# CHM_CPU_FPGA_CLAMP.net
KiCad netlist of a schematic drawn in Altium Designer
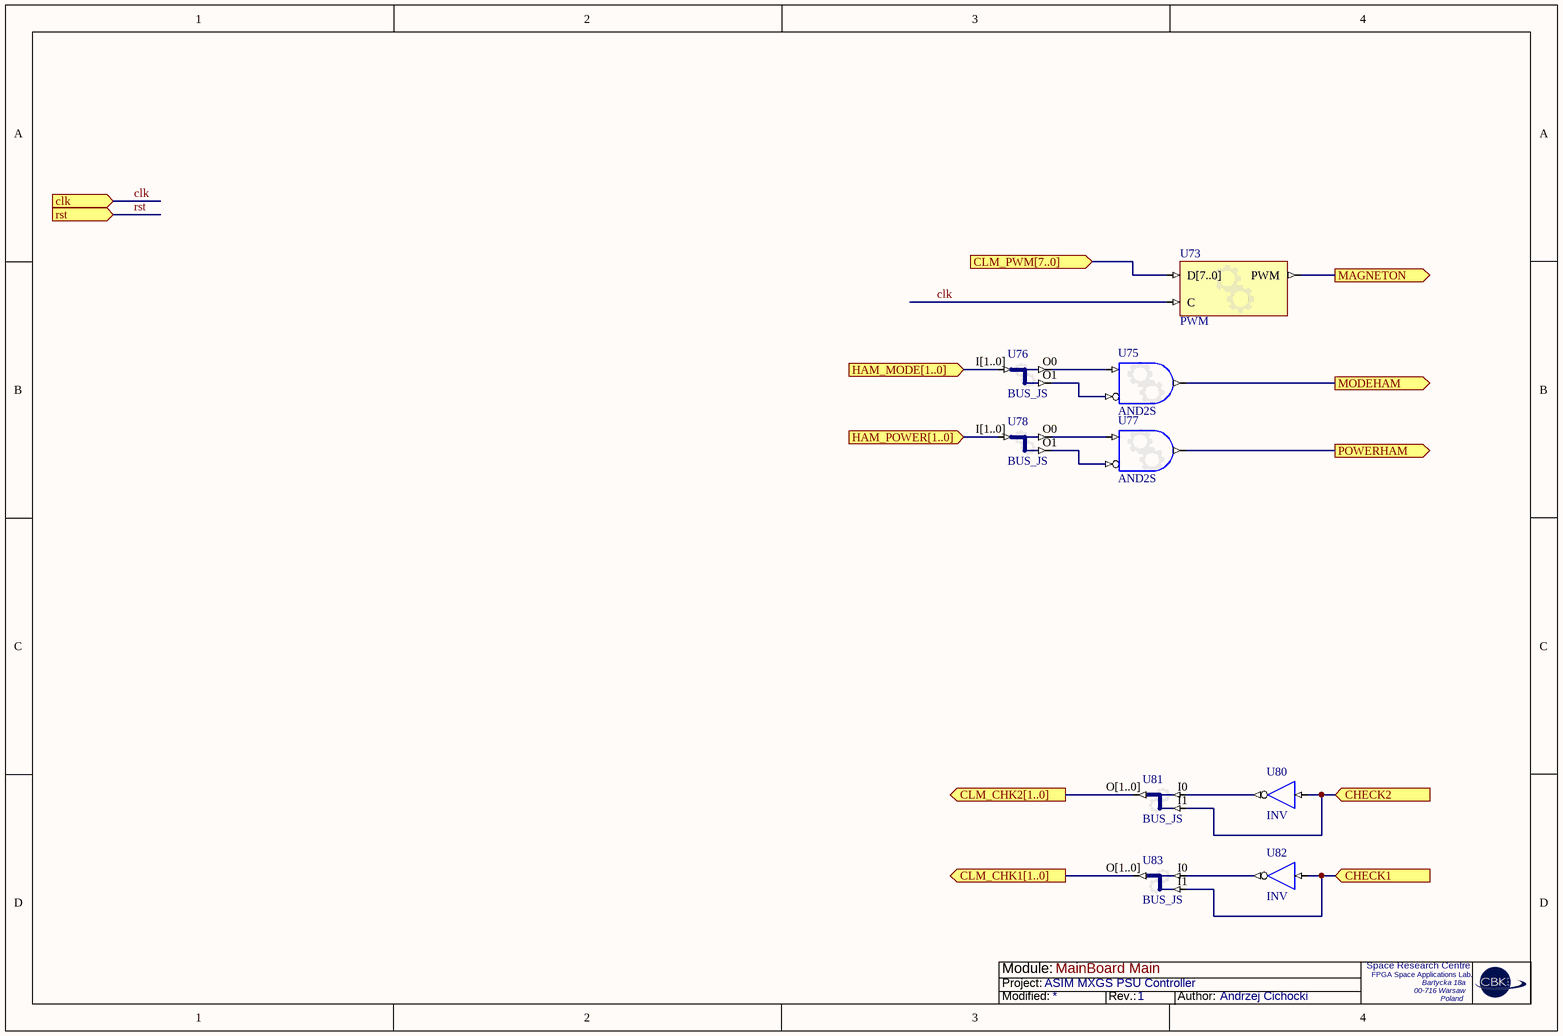
[diagram p0: CHM_CPU_FPGA_CLAMP.SchDoc]

(export (version "E")
  (design (tool "Eeschema 10.0.6"))
  (components
    (comp (ref "U73")
      (value "PWM")
      (description "Configurable PWM")
      (fields (field (name "PUBLISHER") "Altium Limited"))
      (libsource (lib "FPGA Configurable Generic") (part "PWM"))
    )
    (comp (ref "U75")
      (value "AND2S")
      (description "Configurable Generic Gate")
      (fields (field (name "PUBLISHER") "Altium Limited"))
      (libsource (lib "FPGA Configurable Generic") (part "GATE"))
    )
    (comp (ref "U76")
      (value "BUS_JS")
      (description "Configurable Bus Joiner/Splitter")
      (fields (field (name "PUBLISHER") "Altium Limited"))
      (libsource (lib "") (part "BUS_JS_1"))
    )
    (comp (ref "U77")
      (value "AND2S")
      (description "Configurable Generic Gate")
      (fields (field (name "PUBLISHER") "Altium Limited"))
      (libsource (lib "FPGA Configurable Generic") (part "GATE"))
    )
    (comp (ref "U78")
      (value "BUS_JS")
      (description "Configurable Bus Joiner/Splitter")
      (fields (field (name "PUBLISHER") "Altium Limited"))
      (libsource (lib "") (part "BUS_JS_1"))
    )
    (comp (ref "U80")
      (value "INV")
      (description "Inverter")
      (fields (field (name "PUBLISHER") "Altium Limited"))
      (libsource (lib "FPGA Generic") (part "INV"))
    )
    (comp (ref "U81")
      (value "BUS_JS")
      (description "Configurable Bus Joiner/Splitter")
      (fields (field (name "PUBLISHER") "Altium Limited"))
      (libsource (lib "FPGA Configurable Generic") (part "BUS_JS"))
    )
    (comp (ref "U82")
      (value "INV")
      (description "Inverter")
      (fields (field (name "PUBLISHER") "Altium Limited"))
      (libsource (lib "FPGA Generic") (part "INV"))
    )
    (comp (ref "U83")
      (value "BUS_JS")
      (description "Configurable Bus Joiner/Splitter")
      (fields (field (name "PUBLISHER") "Altium Limited"))
      (libsource (lib "FPGA Configurable Generic") (part "BUS_JS"))
    )
  )
  (nets
    (net (code "17") (name "/CHECK1") (class "Default")
      (node (ref "U82") (pin "I") (pinfunction "I_I") (pintype "input"))
      (node (ref "U83") (pin "I1") (pinfunction "I1_I1") (pintype "input"))
    )
    (net (code "18") (name "/CHECK2") (class "Default")
      (node (ref "U80") (pin "I") (pinfunction "I_I") (pintype "input"))
      (node (ref "U81") (pin "I1") (pinfunction "I1_I1") (pintype "input"))
    )
    (net (code "19") (name "/CLM_CHK1[1..0]") (class "Default")
      (node (ref "U83") (pin "O[1..0]") (pinfunction "O[1..0]_O[1..0]") (pintype "output"))
    )
    (net (code "20") (name "/CLM_CHK2[1..0]") (class "Default")
      (node (ref "U81") (pin "O[1..0]") (pinfunction "O[1..0]_O[1..0]") (pintype "output"))
    )
    (net (code "21") (name "/CLM_PWM[7..0]") (class "Default")
      (node (ref "U73") (pin "D[7..0]") (pinfunction "D[7..0]_D[7..0]") (pintype "input"))
    )
    (net (code "22") (name "/HAM_MODE[1..0]") (class "Default")
      (node (ref "U76") (pin "I[1..0]") (pinfunction "I[1..0]_I[1..0]") (pintype "input"))
    )
    (net (code "23") (name "/HAM_POWER[1..0]") (class "Default")
      (node (ref "U78") (pin "I[1..0]") (pinfunction "I[1..0]_I[1..0]") (pintype "input"))
    )
    (net (code "24") (name "/MAGNETON") (class "Default")
      (node (ref "U73") (pin "PWM") (pinfunction "PWM_PWM") (pintype "output"))
    )
    (net (code "25") (name "/MODEHAM") (class "Default")
      (node (ref "U75") (pin "O") (pinfunction "O_O") (pintype "output"))
    )
    (net (code "26") (name "/POWERHAM") (class "Default")
      (node (ref "U77") (pin "O") (pinfunction "O_O") (pintype "output"))
    )
    (net (code "27") (name "/clk") (class "Default")
      (node (ref "U73") (pin "C") (pinfunction "C_C") (pintype "input"))
    )
    (net (code "29") (name "Net-(U75-PadI0)") (class "Default")
      (node (ref "U75") (pin "I0") (pinfunction "I0_I0") (pintype "input"))
      (node (ref "U76") (pin "O0") (pinfunction "O0_O0") (pintype "output"))
    )
    (net (code "30") (name "Net-(U75-PadI1)") (class "Default")
      (node (ref "U75") (pin "I1") (pinfunction "I1_I1") (pintype "input"))
      (node (ref "U76") (pin "O1") (pinfunction "O1_O1") (pintype "output"))
    )
    (net (code "31") (name "Net-(U77-PadI0)") (class "Default")
      (node (ref "U77") (pin "I0") (pinfunction "I0_I0") (pintype "input"))
      (node (ref "U78") (pin "O0") (pinfunction "O0_O0") (pintype "output"))
    )
    (net (code "32") (name "Net-(U77-PadI1)") (class "Default")
      (node (ref "U77") (pin "I1") (pinfunction "I1_I1") (pintype "input"))
      (node (ref "U78") (pin "O1") (pinfunction "O1_O1") (pintype "output"))
    )
    (net (code "33") (name "Net-(U80-PadO)") (class "Default")
      (node (ref "U80") (pin "O") (pinfunction "O_O") (pintype "output"))
      (node (ref "U81") (pin "I0") (pinfunction "I0_I0") (pintype "input"))
    )
    (net (code "34") (name "Net-(U82-PadO)") (class "Default")
      (node (ref "U82") (pin "O") (pinfunction "O_O") (pintype "output"))
      (node (ref "U83") (pin "I0") (pinfunction "I0_I0") (pintype "input"))
    )
  )
)
